# pushbutton.net
KiCad netlist of a schematic drawn in Altium Designer
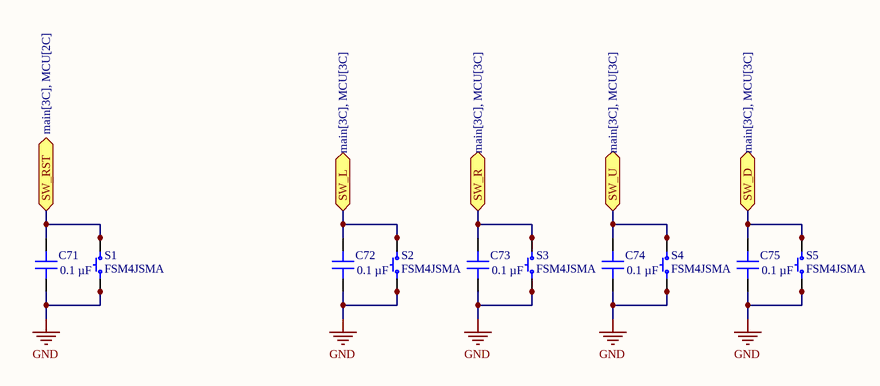
[diagram p0: pushbutton.SchDoc]

(export (version "E")
  (design (tool "Eeschema 10.0.6"))
  (components
    (comp (ref "C71")
      (value "0.1 µF")
      (footprint "CAP 1206_3216 - 0.8MM")
      (description "CAP CER 0.1UF 50V X7R 1206")
      (fields
        (field (name "PART NUMBER") "885012208087")
        (field (name "CAPACITANCE") "0.1 µF")
        (field (name "MANUFACTURER") "Würth Elektronik")
      )
      (libsource (lib "Celestial Altium Library - altium_library") (part "Capacitor"))
    )
    (comp (ref "C72")
      (value "0.1 µF")
      (footprint "CAP 1206_3216 - 0.8MM")
      (description "CAP CER 0.1UF 50V X7R 1206")
      (fields
        (field (name "PART NUMBER") "885012208087")
        (field (name "CAPACITANCE") "0.1 µF")
        (field (name "MANUFACTURER") "Würth Elektronik")
      )
      (libsource (lib "Celestial Altium Library - altium_library") (part "Capacitor"))
    )
    (comp (ref "C73")
      (value "0.1 µF")
      (footprint "CAP 1206_3216 - 0.8MM")
      (description "CAP CER 0.1UF 50V X7R 1206")
      (fields
        (field (name "PART NUMBER") "885012208087")
        (field (name "CAPACITANCE") "0.1 µF")
        (field (name "MANUFACTURER") "Würth Elektronik")
      )
      (libsource (lib "Celestial Altium Library - altium_library") (part "Capacitor"))
    )
    (comp (ref "C74")
      (value "0.1 µF")
      (footprint "CAP 1206_3216 - 0.8MM")
      (description "CAP CER 0.1UF 50V X7R 1206")
      (fields
        (field (name "PART NUMBER") "885012208087")
        (field (name "CAPACITANCE") "0.1 µF")
        (field (name "MANUFACTURER") "Würth Elektronik")
      )
      (libsource (lib "Celestial Altium Library - altium_library") (part "Capacitor"))
    )
    (comp (ref "C75")
      (value "0.1 µF")
      (footprint "CAP 1206_3216 - 0.8MM")
      (description "CAP CER 0.1UF 50V X7R 1206")
      (fields
        (field (name "PART NUMBER") "885012208087")
        (field (name "CAPACITANCE") "0.1 µF")
        (field (name "MANUFACTURER") "Würth Elektronik")
      )
      (libsource (lib "Celestial Altium Library - altium_library") (part "Capacitor"))
    )
    (comp (ref "S1")
      (value "FSM4JSMA")
      (footprint "TE FSM4JSMA")
      (description "SWITCH TACTILE SPST-NO 0.05A 24V")
      (fields (field (name "MANUFACTURER") "TE Connectivity ALCOSWITCH Switches"))
      (libsource (lib "Celestial Altium Library - altium_library") (part "SPST-NO 4 PIN"))
    )
    (comp (ref "S2")
      (value "FSM4JSMA")
      (footprint "TE FSM4JSMA")
      (description "SWITCH TACTILE SPST-NO 0.05A 24V")
      (fields (field (name "MANUFACTURER") "TE Connectivity ALCOSWITCH Switches"))
      (libsource (lib "Celestial Altium Library - altium_library") (part "SPST-NO 4 PIN"))
    )
    (comp (ref "S3")
      (value "FSM4JSMA")
      (footprint "TE FSM4JSMA")
      (description "SWITCH TACTILE SPST-NO 0.05A 24V")
      (fields (field (name "MANUFACTURER") "TE Connectivity ALCOSWITCH Switches"))
      (libsource (lib "Celestial Altium Library - altium_library") (part "SPST-NO 4 PIN"))
    )
    (comp (ref "S4")
      (value "FSM4JSMA")
      (footprint "TE FSM4JSMA")
      (description "SWITCH TACTILE SPST-NO 0.05A 24V")
      (fields (field (name "MANUFACTURER") "TE Connectivity ALCOSWITCH Switches"))
      (libsource (lib "Celestial Altium Library - altium_library") (part "SPST-NO 4 PIN"))
    )
    (comp (ref "S5")
      (value "FSM4JSMA")
      (footprint "TE FSM4JSMA")
      (description "SWITCH TACTILE SPST-NO 0.05A 24V")
      (fields (field (name "MANUFACTURER") "TE Connectivity ALCOSWITCH Switches"))
      (libsource (lib "Celestial Altium Library - altium_library") (part "SPST-NO 4 PIN"))
    )
  )
  (nets
    (net (code "1") (name "/SW_D") (class "Default")
      (node (ref "C75") (pin "2") (pinfunction "2_2") (pintype "passive"))
      (node (ref "S5") (pin "3") (pinfunction "3_3") (pintype "passive"))
      (node (ref "S5") (pin "4") (pinfunction "4_4") (pintype "passive"))
    )
    (net (code "2") (name "/SW_L") (class "Default")
      (node (ref "C72") (pin "2") (pinfunction "2_2") (pintype "passive"))
      (node (ref "S2") (pin "3") (pinfunction "3_3") (pintype "passive"))
      (node (ref "S2") (pin "4") (pinfunction "4_4") (pintype "passive"))
    )
    (net (code "3") (name "/SW_R") (class "Default")
      (node (ref "C73") (pin "2") (pinfunction "2_2") (pintype "passive"))
      (node (ref "S3") (pin "3") (pinfunction "3_3") (pintype "passive"))
      (node (ref "S3") (pin "4") (pinfunction "4_4") (pintype "passive"))
    )
    (net (code "4") (name "/SW_RST") (class "Default")
      (node (ref "C71") (pin "2") (pinfunction "2_2") (pintype "passive"))
      (node (ref "S1") (pin "3") (pinfunction "3_3") (pintype "passive"))
      (node (ref "S1") (pin "4") (pinfunction "4_4") (pintype "passive"))
    )
    (net (code "5") (name "/SW_U") (class "Default")
      (node (ref "C74") (pin "2") (pinfunction "2_2") (pintype "passive"))
      (node (ref "S4") (pin "3") (pinfunction "3_3") (pintype "passive"))
      (node (ref "S4") (pin "4") (pinfunction "4_4") (pintype "passive"))
    )
    (net (code "6") (name "GND") (class "Default")
      (node (ref "C71") (pin "1") (pinfunction "1_1") (pintype "passive"))
      (node (ref "C72") (pin "1") (pinfunction "1_1") (pintype "passive"))
      (node (ref "C73") (pin "1") (pinfunction "1_1") (pintype "passive"))
      (node (ref "C74") (pin "1") (pinfunction "1_1") (pintype "passive"))
      (node (ref "C75") (pin "1") (pinfunction "1_1") (pintype "passive"))
      (node (ref "S1") (pin "1") (pinfunction "1_1") (pintype "passive"))
      (node (ref "S1") (pin "2") (pinfunction "2_2") (pintype "passive"))
      (node (ref "S2") (pin "1") (pinfunction "1_1") (pintype "passive"))
      (node (ref "S2") (pin "2") (pinfunction "2_2") (pintype "passive"))
      (node (ref "S3") (pin "1") (pinfunction "1_1") (pintype "passive"))
      (node (ref "S3") (pin "2") (pinfunction "2_2") (pintype "passive"))
      (node (ref "S4") (pin "1") (pinfunction "1_1") (pintype "passive"))
      (node (ref "S4") (pin "2") (pinfunction "2_2") (pintype "passive"))
      (node (ref "S5") (pin "1") (pinfunction "1_1") (pintype "passive"))
      (node (ref "S5") (pin "2") (pinfunction "2_2") (pintype "passive"))
    )
  )
)
